# Docking.net
KiCad netlist of a schematic drawn in Altium Designer
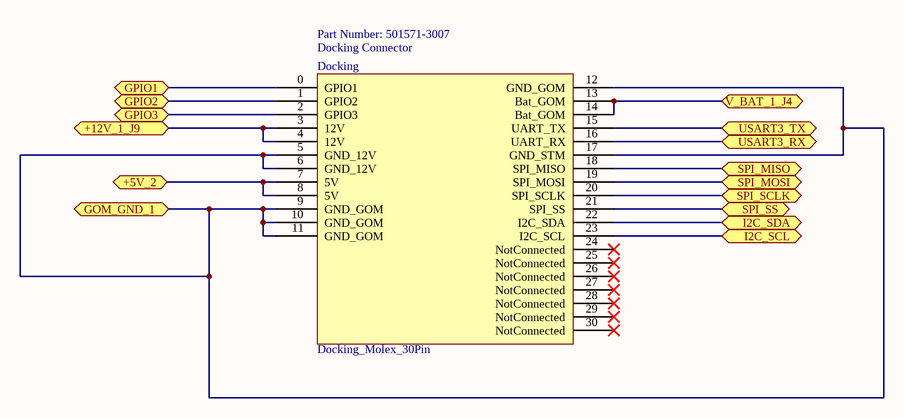
[diagram p0: Docking.SchDoc]

(export (version "E")
  (design (tool "Eeschema 10.0.6"))
  (components
    (comp (ref "Docking")
      (value "Docking_Molex_30Pin")
      (footprint "UmbilicalConnectors:Docking_Molex_30Pin")
      (description "24 Pin Connector")
      (libsource (lib "UmbilicalBoardV2") (part "Docking_Molex_30Pin"))
    )
  )
  (nets
    (net (code "1") (name "/+5V_2") (class "Default")
      (node (ref "Docking") (pin "7") (pinfunction "5V_7") (pintype "passive"))
      (node (ref "Docking") (pin "8") (pinfunction "5V_8") (pintype "passive"))
    )
    (net (code "2") (name "/+12V_1_J9") (class "Default")
      (node (ref "Docking") (pin "3") (pinfunction "12V_3") (pintype "passive"))
      (node (ref "Docking") (pin "4") (pinfunction "12V_4") (pintype "passive"))
    )
    (net (code "3") (name "/GOM_GND_1") (class "Default")
      (node (ref "Docking") (pin "10") (pinfunction "GND_GOM_10") (pintype "passive"))
      (node (ref "Docking") (pin "11") (pinfunction "GND_GOM_11") (pintype "passive"))
      (node (ref "Docking") (pin "12") (pinfunction "GND_GOM_12") (pintype "passive"))
      (node (ref "Docking") (pin "17") (pinfunction "GND_STM_17") (pintype "passive"))
      (node (ref "Docking") (pin "5") (pinfunction "GND_12V_5") (pintype "passive"))
      (node (ref "Docking") (pin "6") (pinfunction "GND_12V_6") (pintype "passive"))
      (node (ref "Docking") (pin "9") (pinfunction "GND_GOM_9") (pintype "passive"))
    )
    (net (code "4") (name "/GPIO1") (class "Default")
      (node (ref "Docking") (pin "0") (pinfunction "GPIO1_0") (pintype "passive"))
    )
    (net (code "5") (name "/GPIO2") (class "Default")
      (node (ref "Docking") (pin "1") (pinfunction "GPIO2_1") (pintype "passive"))
    )
    (net (code "6") (name "/GPIO3") (class "Default")
      (node (ref "Docking") (pin "2") (pinfunction "GPIO3_2") (pintype "passive"))
    )
    (net (code "7") (name "/I2C_SCL") (class "Default")
      (node (ref "Docking") (pin "23") (pinfunction "I2C_SCL_23") (pintype "passive"))
    )
    (net (code "8") (name "/I2C_SDA") (class "Default")
      (node (ref "Docking") (pin "22") (pinfunction "I2C_SDA_22") (pintype "passive"))
    )
    (net (code "9") (name "/SPI_MISO") (class "Default")
      (node (ref "Docking") (pin "18") (pinfunction "SPI_MISO_18") (pintype "passive"))
    )
    (net (code "10") (name "/SPI_MOSI") (class "Default")
      (node (ref "Docking") (pin "19") (pinfunction "SPI_MOSI_19") (pintype "passive"))
    )
    (net (code "11") (name "/SPI_SCLK") (class "Default")
      (node (ref "Docking") (pin "20") (pinfunction "SPI_SCLK_20") (pintype "passive"))
    )
    (net (code "12") (name "/SPI_SS") (class "Default")
      (node (ref "Docking") (pin "21") (pinfunction "SPI_SS_21") (pintype "passive"))
    )
    (net (code "13") (name "/USART3_RX") (class "Default")
      (node (ref "Docking") (pin "16") (pinfunction "UART_RX_16") (pintype "passive"))
    )
    (net (code "14") (name "/USART3_TX") (class "Default")
      (node (ref "Docking") (pin "15") (pinfunction "UART_TX_15") (pintype "passive"))
    )
    (net (code "15") (name "/V_BAT_1_J4") (class "Default")
      (node (ref "Docking") (pin "13") (pinfunction "Bat_GOM_13") (pintype "passive"))
      (node (ref "Docking") (pin "14") (pinfunction "Bat_GOM_14") (pintype "passive"))
    )
    (net (code "16") (name "unconnected-(Docking-NotConnected-Pad24)") (class "Default")
      (node (ref "Docking") (pin "24") (pinfunction "NotConnected_24") (pintype "passive+no_connect"))
    )
    (net (code "17") (name "unconnected-(Docking-NotConnected-Pad25)") (class "Default")
      (node (ref "Docking") (pin "25") (pinfunction "NotConnected_25") (pintype "passive+no_connect"))
    )
    (net (code "18") (name "unconnected-(Docking-NotConnected-Pad26)") (class "Default")
      (node (ref "Docking") (pin "26") (pinfunction "NotConnected_26") (pintype "passive+no_connect"))
    )
    (net (code "19") (name "unconnected-(Docking-NotConnected-Pad27)") (class "Default")
      (node (ref "Docking") (pin "27") (pinfunction "NotConnected_27") (pintype "passive+no_connect"))
    )
    (net (code "20") (name "unconnected-(Docking-NotConnected-Pad28)") (class "Default")
      (node (ref "Docking") (pin "28") (pinfunction "NotConnected_28") (pintype "passive+no_connect"))
    )
    (net (code "21") (name "unconnected-(Docking-NotConnected-Pad29)") (class "Default")
      (node (ref "Docking") (pin "29") (pinfunction "NotConnected_29") (pintype "passive+no_connect"))
    )
    (net (code "22") (name "unconnected-(Docking-NotConnected-Pad30)") (class "Default")
      (node (ref "Docking") (pin "30") (pinfunction "NotConnected_30") (pintype "passive+no_connect"))
    )
  )
)
